# TLV493D-Board_RevA.net
KiCad netlist of a schematic drawn in EAGLE
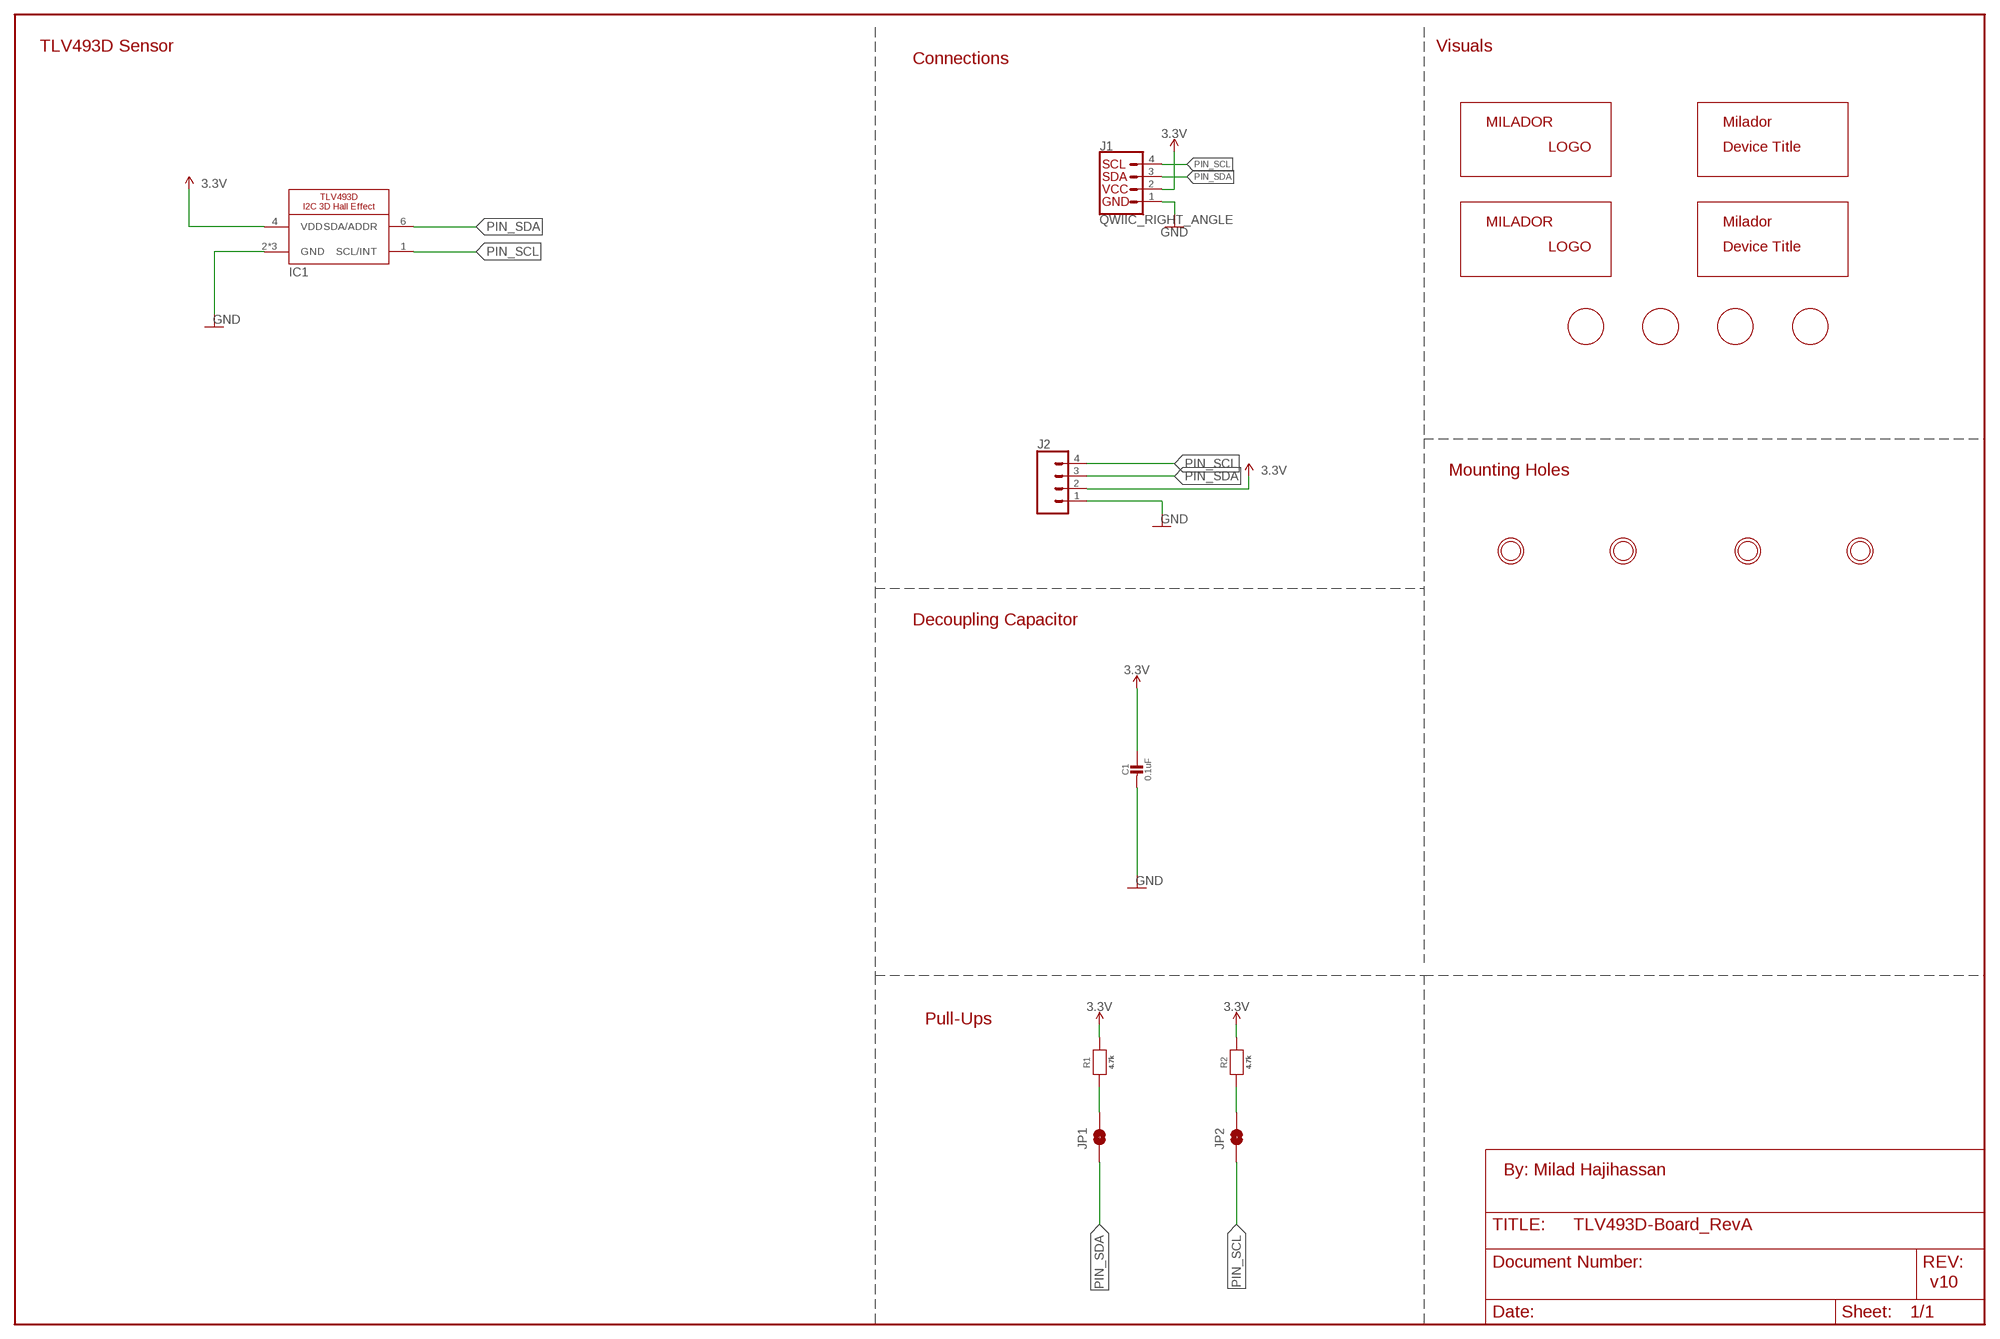
[diagram p0: schematic, sheet 1]

(export (version "E")
  (design (tool "Eeschema 10.0.6"))
  (components
    (comp (ref "C1")
      (value "0.1uF")
      (footprint "eagle-import:0805")
      (libsource (lib "eagle-import") (part "CAP_CERAMIC-0805"))
    )
    (comp (ref "IC1")
      (value "TLV493D")
      (footprint "eagle-import:SOT23-6")
      (libsource (lib "eagle-import") (part "TLV493D"))
    )
    (comp (ref "J1")
      (value "QWIIC_RIGHT_ANGLE")
      (footprint "eagle-import:CONNECTORS_JST04_1MM_RA")
      (fields (field (name "PROD_ID") "CONN-13694"))
      (libsource (lib "eagle-import") (part "QWIIC_CONNECTORSJS-1MM"))
    )
    (comp (ref "J2")
      (value "CONNECTORS_CONN_041X04_NO_SILK")
      (footprint "eagle-import:CONNECTORS_1X04_NO_SILK")
      (libsource (lib "eagle-import") (part "CONNECTORS_CONN_041X04_NO_SILK"))
    )
    (comp (ref "JP1")
      (value "JUMPERS-SMT_2_NC_TRACE_SILK")
      (footprint "eagle-import:JUMPERS_SMT-JUMPER_2_NC_TRACE_SILK")
      (libsource (lib "eagle-import") (part "JUMPERS-SMT_2_NC_TRACE_SILK"))
    )
    (comp (ref "JP2")
      (value "JUMPERS-SMT_2_NC_TRACE_SILK")
      (footprint "eagle-import:JUMPERS_SMT-JUMPER_2_NC_TRACE_SILK")
      (libsource (lib "eagle-import") (part "JUMPERS-SMT_2_NC_TRACE_SILK"))
    )
    (comp (ref "LABEL_3V_BOTTOM")
      (value "MILADOR-LABEL-3V")
      (footprint "eagle-import:LABEL-3V")
      (libsource (lib "eagle-import") (part "MILADOR-LABEL-3V"))
    )
    (comp (ref "LABEL_GND_BOTTOM")
      (value "MILADOR-LABEL-GND")
      (footprint "eagle-import:LABEL-GND")
      (libsource (lib "eagle-import") (part "MILADOR-LABEL-GND"))
    )
    (comp (ref "LABEL_MILADOR_BOTTOM")
      (value "MILADOR-LOGO-")
      (footprint "eagle-import:MILADOR_LOGO1")
      (libsource (lib "eagle-import") (part "MILADOR-LOGO-"))
    )
    (comp (ref "LABEL_MILADOR_TLV493D_BOTTOM")
      (value "MILADOR-DEVICE-TLV493D_BOARD")
      (footprint "eagle-import:MILADOR_TLV493D_BOARD")
      (libsource (lib "eagle-import") (part "MILADOR-DEVICE-TLV493D_BOARD"))
    )
    (comp (ref "LABEL_MILADOR_TLV493D_TOP")
      (value "MILADOR-DEVICE-TLV493D_BOARD")
      (footprint "eagle-import:MILADOR_TLV493D_BOARD")
      (libsource (lib "eagle-import") (part "MILADOR-DEVICE-TLV493D_BOARD"))
    )
    (comp (ref "LABEL_MILADOR_TOP")
      (value "MILADOR-LOGO-")
      (footprint "eagle-import:MILADOR_LOGO1")
      (libsource (lib "eagle-import") (part "MILADOR-LOGO-"))
    )
    (comp (ref "LABE_SCL_BOTTOM")
      (value "MILADOR-LABEL-SCL")
      (footprint "eagle-import:LABEL-SCL")
      (libsource (lib "eagle-import") (part "MILADOR-LABEL-SCL"))
    )
    (comp (ref "LABE_SDA_BOTTOM")
      (value "MILADOR-LABEL-SDA")
      (footprint "eagle-import:LABEL-SDA")
      (libsource (lib "eagle-import") (part "MILADOR-LABEL-SDA"))
    )
    (comp (ref "M1")
      (value "MOUNTINGHOLE2.5")
      (footprint "eagle-import:MOUNTINGHOLE_2.5_PLATED")
      (libsource (lib "eagle-import") (part "MOUNTINGHOLE2.5"))
    )
    (comp (ref "M2")
      (value "MOUNTINGHOLE2.5")
      (footprint "eagle-import:MOUNTINGHOLE_2.5_PLATED")
      (libsource (lib "eagle-import") (part "MOUNTINGHOLE2.5"))
    )
    (comp (ref "M3")
      (value "MOUNTINGHOLE2.5")
      (footprint "eagle-import:MOUNTINGHOLE_2.5_PLATED")
      (libsource (lib "eagle-import") (part "MOUNTINGHOLE2.5"))
    )
    (comp (ref "M4")
      (value "MOUNTINGHOLE2.5")
      (footprint "eagle-import:MOUNTINGHOLE_2.5_PLATED")
      (libsource (lib "eagle-import") (part "MOUNTINGHOLE2.5"))
    )
    (comp (ref "R1")
      (value "4.7k")
      (footprint "eagle-import:0603-NO")
      (libsource (lib "eagle-import") (part "RESISTOR-0603-NOOUT"))
    )
    (comp (ref "R2")
      (value "4.7k")
      (footprint "eagle-import:0603-NO")
      (libsource (lib "eagle-import") (part "RESISTOR-0603-NOOUT"))
    )
  )
  (nets
    (net (code "1") (name "3.3V") (class "Default")
      (node (ref "C1") (pin "1") (pinfunction "1_1") (pintype "passive"))
      (node (ref "IC1") (pin "4") (pinfunction "VDD_4") (pintype "power_in"))
      (node (ref "J1") (pin "2") (pinfunction "2_2") (pintype "power_in"))
      (node (ref "J2") (pin "2") (pinfunction "2_2") (pintype "passive"))
      (node (ref "R1") (pin "2") (pinfunction "2_2") (pintype "passive"))
      (node (ref "R2") (pin "2") (pinfunction "2_2") (pintype "passive"))
    )
    (net (code "2") (name "GND") (class "Default")
      (node (ref "C1") (pin "2") (pinfunction "2_2") (pintype "passive"))
      (node (ref "IC1") (pin "2") (pinfunction "GND_2") (pintype "power_in"))
      (node (ref "IC1") (pin "3") (pinfunction "GND_3") (pintype "power_in"))
      (node (ref "IC1") (pin "5") (pinfunction "GND_5") (pintype "power_in"))
      (node (ref "J1") (pin "1") (pinfunction "1_1") (pintype "power_in"))
      (node (ref "J2") (pin "1") (pinfunction "1_1") (pintype "passive"))
    )
    (net (code "3") (name "Net-(JP1-Pad2)") (class "Default")
      (node (ref "JP1") (pin "2") (pinfunction "2_2") (pintype "passive"))
      (node (ref "R1") (pin "1") (pinfunction "1_1") (pintype "passive"))
    )
    (net (code "4") (name "Net-(JP2-Pad2)") (class "Default")
      (node (ref "JP2") (pin "2") (pinfunction "2_2") (pintype "passive"))
      (node (ref "R2") (pin "1") (pinfunction "1_1") (pintype "passive"))
    )
    (net (code "5") (name "PIN_SCL") (class "Default")
      (node (ref "IC1") (pin "1") (pinfunction "SCL/INT_1") (pintype "bidirectional"))
      (node (ref "J1") (pin "4") (pinfunction "4_4") (pintype "passive"))
      (node (ref "J2") (pin "4") (pinfunction "4_4") (pintype "passive"))
      (node (ref "JP2") (pin "1") (pinfunction "1_1") (pintype "passive"))
    )
    (net (code "6") (name "PIN_SDA") (class "Default")
      (node (ref "IC1") (pin "6") (pinfunction "SDA/ADDR_6") (pintype "bidirectional"))
      (node (ref "J1") (pin "3") (pinfunction "3_3") (pintype "passive"))
      (node (ref "J2") (pin "3") (pinfunction "3_3") (pintype "passive"))
      (node (ref "JP1") (pin "1") (pinfunction "1_1") (pintype "passive"))
    )
  )
)
